# PowerSupply.net
KiCad netlist of a schematic drawn in Altium Designer
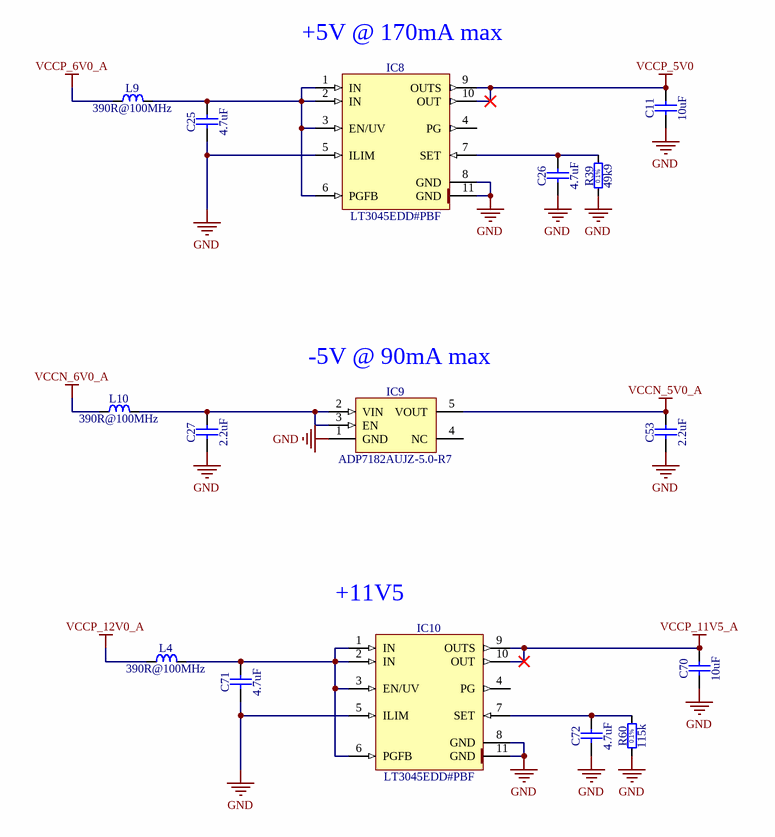
[diagram p0: PowerSupply.SchDoc]

(export (version "E")
  (design (tool "Eeschema 10.0.6"))
  (components
    (comp (ref "C11")
      (value "10uF")
      (footprint "CAPC1608X87N")
      (description "Non-polarised capacitor")
      (fields
        (field (name "PART NUMBER") "CC0603_10UF_6.3V_20%_X5R")
        (field (name "VOLTAGE") "6.3V")
        (field (name "AUTHOR") "CERN DEM JLC")
      )
      (libsource (lib "Capacitors") (part "Capacitor - non polarized"))
    )
    (comp (ref "C25")
      (value "4.7uF")
      (footprint "CAPC1709X95N")
      (description "Non-polarised capacitor")
      (fields
        (field (name "PART NUMBER") "CC0603_4.7UF_16V_10%_X5R")
        (field (name "VOLTAGE") "16V")
        (field (name "AUTHOR") "CERN DEM JLC")
      )
      (libsource (lib "Capacitors") (part "Capacitor - non polarized"))
    )
    (comp (ref "C26")
      (value "4.7uF")
      (footprint "CAPC1709X95N")
      (description "Non-polarised capacitor")
      (fields
        (field (name "PART NUMBER") "CC0603_4.7UF_16V_10%_X5R")
        (field (name "VOLTAGE") "16V")
        (field (name "AUTHOR") "CERN DEM JLC")
      )
      (libsource (lib "Capacitors") (part "Capacitor - non polarized"))
    )
    (comp (ref "C27")
      (value "2.2uF")
      (footprint "CAPC1608X90N")
      (description "Non-polarised capacitor")
      (fields
        (field (name "PART NUMBER") "CC0603_2.2UF_10V_20%_X7R")
        (field (name "VOLTAGE") "10V")
        (field (name "AUTHOR") "CERN DEM JLC")
      )
      (libsource (lib "Capacitors") (part "Capacitor - non polarized"))
    )
    (comp (ref "C53")
      (value "2.2uF")
      (footprint "CAPC1608X90N")
      (description "Non-polarised capacitor")
      (fields
        (field (name "PART NUMBER") "CC0603_2.2UF_10V_20%_X7R")
        (field (name "VOLTAGE") "10V")
        (field (name "AUTHOR") "CERN DEM JLC")
      )
      (libsource (lib "Capacitors") (part "Capacitor - non polarized"))
    )
    (comp (ref "C70")
      (value "10uF")
      (footprint "CAPC1608X87N")
      (description "Non-polarised capacitor")
      (fields
        (field (name "PART NUMBER") "CC0603_10UF_6.3V_20%_X5R")
        (field (name "VOLTAGE") "6.3V")
        (field (name "AUTHOR") "CERN DEM JLC")
      )
      (libsource (lib "Capacitors") (part "Capacitor - non polarized"))
    )
    (comp (ref "C71")
      (value "4.7uF")
      (footprint "CAPC1709X95N")
      (description "Non-polarised capacitor")
      (fields
        (field (name "PART NUMBER") "CC0603_4.7UF_16V_10%_X5R")
        (field (name "VOLTAGE") "16V")
        (field (name "AUTHOR") "CERN DEM JLC")
      )
      (libsource (lib "Capacitors") (part "Capacitor - non polarized"))
    )
    (comp (ref "C72")
      (value "4.7uF")
      (footprint "CAPC1709X95N")
      (description "Non-polarised capacitor")
      (fields
        (field (name "PART NUMBER") "CC0603_4.7UF_16V_10%_X5R")
        (field (name "VOLTAGE") "16V")
        (field (name "AUTHOR") "CERN DEM JLC")
      )
      (libsource (lib "Capacitors") (part "Capacitor - non polarized"))
    )
    (comp (ref "IC8")
      (value "LT3045EDD#PBF")
      (footprint "SON50P300X300X80-11N-R175X248")
      (description "20V, 500mA, Ultralow Noise, Ultrahigh PSRR Linear Regulator")
      (fields (field (name "MANUFACTURER") "LINEAR TECHNOLOGY") (field (name "AUTHOR") "CERN DEM JLC"))
      (libsource (lib "ICs And Semiconductors") (part "LT3045EDD"))
    )
    (comp (ref "IC9")
      (value "ADP7182AUJZ-5.0-R7")
      (footprint "SOT95P280X90-5N")
      (description "–5V, 200 mA, Low Noise, Linear Regulator")
      (fields (field (name "MANUFACTURER") "ANALOG DEVICES") (field (name "AUTHOR") "CERN DEM JLC"))
      (libsource (lib "ICs And Semiconductors") (part "ADP7182AUJZ-X.X-R7"))
    )
    (comp (ref "IC10")
      (value "LT3045EDD#PBF")
      (footprint "SON50P300X300X80-11N-R175X248")
      (description "20V, 500mA, Ultralow Noise, Ultrahigh PSRR Linear Regulator")
      (fields (field (name "MANUFACTURER") "LINEAR TECHNOLOGY") (field (name "AUTHOR") "CERN DEM JLC"))
      (libsource (lib "ICs And Semiconductors") (part "LT3045EDD"))
    )
    (comp (ref "L4")
      (value "390R@100MHz")
      (footprint "INDC1608X95N")
      (description "Inductor")
      (fields
        (field (name "PART NUMBER") "IND0603_TDK_MPZ1608R391A")
        (field (name "POWER") "1.2A")
        (field (name "AUTHOR") "CERN DEM JLC")
      )
      (libsource (lib "Inductors & Transformers") (part "Inductor"))
    )
    (comp (ref "L9")
      (value "390R@100MHz")
      (footprint "INDC1608X95N")
      (description "Inductor")
      (fields
        (field (name "PART NUMBER") "IND0603_TDK_MPZ1608R391A")
        (field (name "POWER") "1.2A")
        (field (name "AUTHOR") "CERN DEM JLC")
      )
      (libsource (lib "Inductors & Transformers") (part "Inductor"))
    )
    (comp (ref "L10")
      (value "390R@100MHz")
      (footprint "INDC1608X95N")
      (description "Inductor")
      (fields
        (field (name "PART NUMBER") "IND0603_TDK_MPZ1608R391A")
        (field (name "POWER") "1.2A")
        (field (name "AUTHOR") "CERN DEM JLC")
      )
      (libsource (lib "Inductors & Transformers") (part "Inductor"))
    )
    (comp (ref "R39")
      (value "49k9")
      (footprint "RESC1608X55N")
      (description "Resistor - 0.1%")
      (fields
        (field (name "PART NUMBER") "R0603_49K9_0.1%_0.063W_10PPM")
        (field (name "POWER") "0.063W")
        (field (name "AUTHOR") "CERN DEM JLC")
      )
      (libsource (lib "Resistors") (part "Resistor - 0.1%"))
    )
    (comp (ref "R60")
      (value "115k")
      (footprint "RESC1608X55N")
      (description "Resistor - 0.1%")
      (fields
        (field (name "PART NUMBER") "R0603_115K_0.1%_0.063W_10PPM")
        (field (name "POWER") "0.063W")
        (field (name "AUTHOR") "CERN DEM JLC")
      )
      (libsource (lib "Resistors") (part "Resistor - 0.1%"))
    )
  )
  (nets
    (net (code "1") (name "GND") (class "Default")
      (node (ref "C11") (pin "1") (pinfunction "1_1") (pintype "passive"))
      (node (ref "C25") (pin "1") (pinfunction "1_1") (pintype "passive"))
      (node (ref "C26") (pin "1") (pinfunction "1_1") (pintype "passive"))
      (node (ref "C27") (pin "1") (pinfunction "1_1") (pintype "passive"))
      (node (ref "C53") (pin "1") (pinfunction "1_1") (pintype "passive"))
      (node (ref "C70") (pin "1") (pinfunction "1_1") (pintype "passive"))
      (node (ref "C71") (pin "1") (pinfunction "1_1") (pintype "passive"))
      (node (ref "C72") (pin "1") (pinfunction "1_1") (pintype "passive"))
      (node (ref "IC10") (pin "11") (pinfunction "GND_11") (pintype "power_in"))
      (node (ref "IC10") (pin "5") (pinfunction "ILIM_5") (pintype "input"))
      (node (ref "IC10") (pin "8") (pinfunction "GND_8") (pintype "power_in"))
      (node (ref "IC8") (pin "11") (pinfunction "GND_11") (pintype "power_in"))
      (node (ref "IC8") (pin "5") (pinfunction "ILIM_5") (pintype "input"))
      (node (ref "IC8") (pin "8") (pinfunction "GND_8") (pintype "power_in"))
      (node (ref "IC9") (pin "1") (pinfunction "GND_1") (pintype "power_in"))
      (node (ref "R39") (pin "1") (pinfunction "1_1") (pintype "passive"))
      (node (ref "R60") (pin "1") (pinfunction "1_1") (pintype "passive"))
    )
    (net (code "2") (name "Net-(IC8-EN{slash}UV)") (class "Default")
      (node (ref "C25") (pin "2") (pinfunction "2_2") (pintype "passive"))
      (node (ref "IC8") (pin "1") (pinfunction "IN_1") (pintype "input"))
      (node (ref "IC8") (pin "2") (pinfunction "IN_2") (pintype "input"))
      (node (ref "IC8") (pin "3") (pinfunction "EN/UV_3") (pintype "input"))
      (node (ref "IC8") (pin "6") (pinfunction "PGFB_6") (pintype "input"))
      (node (ref "L9") (pin "2") (pinfunction "2_2") (pintype "passive"))
    )
    (net (code "3") (name "Net-(IC8-SET)") (class "Default")
      (node (ref "C26") (pin "2") (pinfunction "2_2") (pintype "passive"))
      (node (ref "IC8") (pin "7") (pinfunction "SET_7") (pintype "input"))
      (node (ref "R39") (pin "2") (pinfunction "2_2") (pintype "passive"))
    )
    (net (code "4") (name "Net-(IC9-EN)") (class "Default")
      (node (ref "C27") (pin "2") (pinfunction "2_2") (pintype "passive"))
      (node (ref "IC9") (pin "2") (pinfunction "VIN_2") (pintype "input"))
      (node (ref "IC9") (pin "3") (pinfunction "EN_3") (pintype "input"))
      (node (ref "L10") (pin "2") (pinfunction "2_2") (pintype "passive"))
    )
    (net (code "5") (name "Net-(IC10-EN{slash}UV)") (class "Default")
      (node (ref "C71") (pin "2") (pinfunction "2_2") (pintype "passive"))
      (node (ref "IC10") (pin "1") (pinfunction "IN_1") (pintype "input"))
      (node (ref "IC10") (pin "2") (pinfunction "IN_2") (pintype "input"))
      (node (ref "IC10") (pin "3") (pinfunction "EN/UV_3") (pintype "input"))
      (node (ref "IC10") (pin "6") (pinfunction "PGFB_6") (pintype "input"))
      (node (ref "L4") (pin "2") (pinfunction "2_2") (pintype "passive"))
    )
    (net (code "6") (name "Net-(IC10-SET)") (class "Default")
      (node (ref "C72") (pin "2") (pinfunction "2_2") (pintype "passive"))
      (node (ref "IC10") (pin "7") (pinfunction "SET_7") (pintype "input"))
      (node (ref "R60") (pin "2") (pinfunction "2_2") (pintype "passive"))
    )
    (net (code "7") (name "VCCN_5V0_A") (class "Default")
      (node (ref "C53") (pin "2") (pinfunction "2_2") (pintype "passive"))
      (node (ref "IC9") (pin "5") (pinfunction "VOUT_5") (pintype "power_in"))
    )
    (net (code "8") (name "VCCN_6V0_A") (class "Default")
      (node (ref "L10") (pin "1") (pinfunction "1_1") (pintype "passive"))
    )
    (net (code "9") (name "VCCP_5V0") (class "Default")
      (node (ref "C11") (pin "2") (pinfunction "2_2") (pintype "passive"))
      (node (ref "IC8") (pin "10") (pinfunction "OUT_10") (pintype "output"))
      (node (ref "IC8") (pin "9") (pinfunction "OUTS_9") (pintype "output"))
    )
    (net (code "10") (name "VCCP_6V0_A") (class "Default")
      (node (ref "L9") (pin "1") (pinfunction "1_1") (pintype "passive"))
    )
    (net (code "11") (name "VCCP_11V5_A") (class "Default")
      (node (ref "C70") (pin "2") (pinfunction "2_2") (pintype "passive"))
      (node (ref "IC10") (pin "10") (pinfunction "OUT_10") (pintype "output"))
      (node (ref "IC10") (pin "9") (pinfunction "OUTS_9") (pintype "output"))
    )
    (net (code "12") (name "VCCP_12V0_A") (class "Default")
      (node (ref "L4") (pin "1") (pinfunction "1_1") (pintype "passive"))
    )
    (net (code "13") (name "unconnected-(IC8-PG-Pad4)") (class "Default")
      (node (ref "IC8") (pin "4") (pinfunction "PG_4") (pintype "output"))
    )
    (net (code "14") (name "unconnected-(IC9-NC-Pad4)") (class "Default")
      (node (ref "IC9") (pin "4") (pinfunction "NC_4") (pintype "passive"))
    )
    (net (code "15") (name "unconnected-(IC10-PG-Pad4)") (class "Default")
      (node (ref "IC10") (pin "4") (pinfunction "PG_4") (pintype "output"))
    )
  )
)
